# Sheet1.net
KiCad netlist of a schematic drawn in Altium Designer
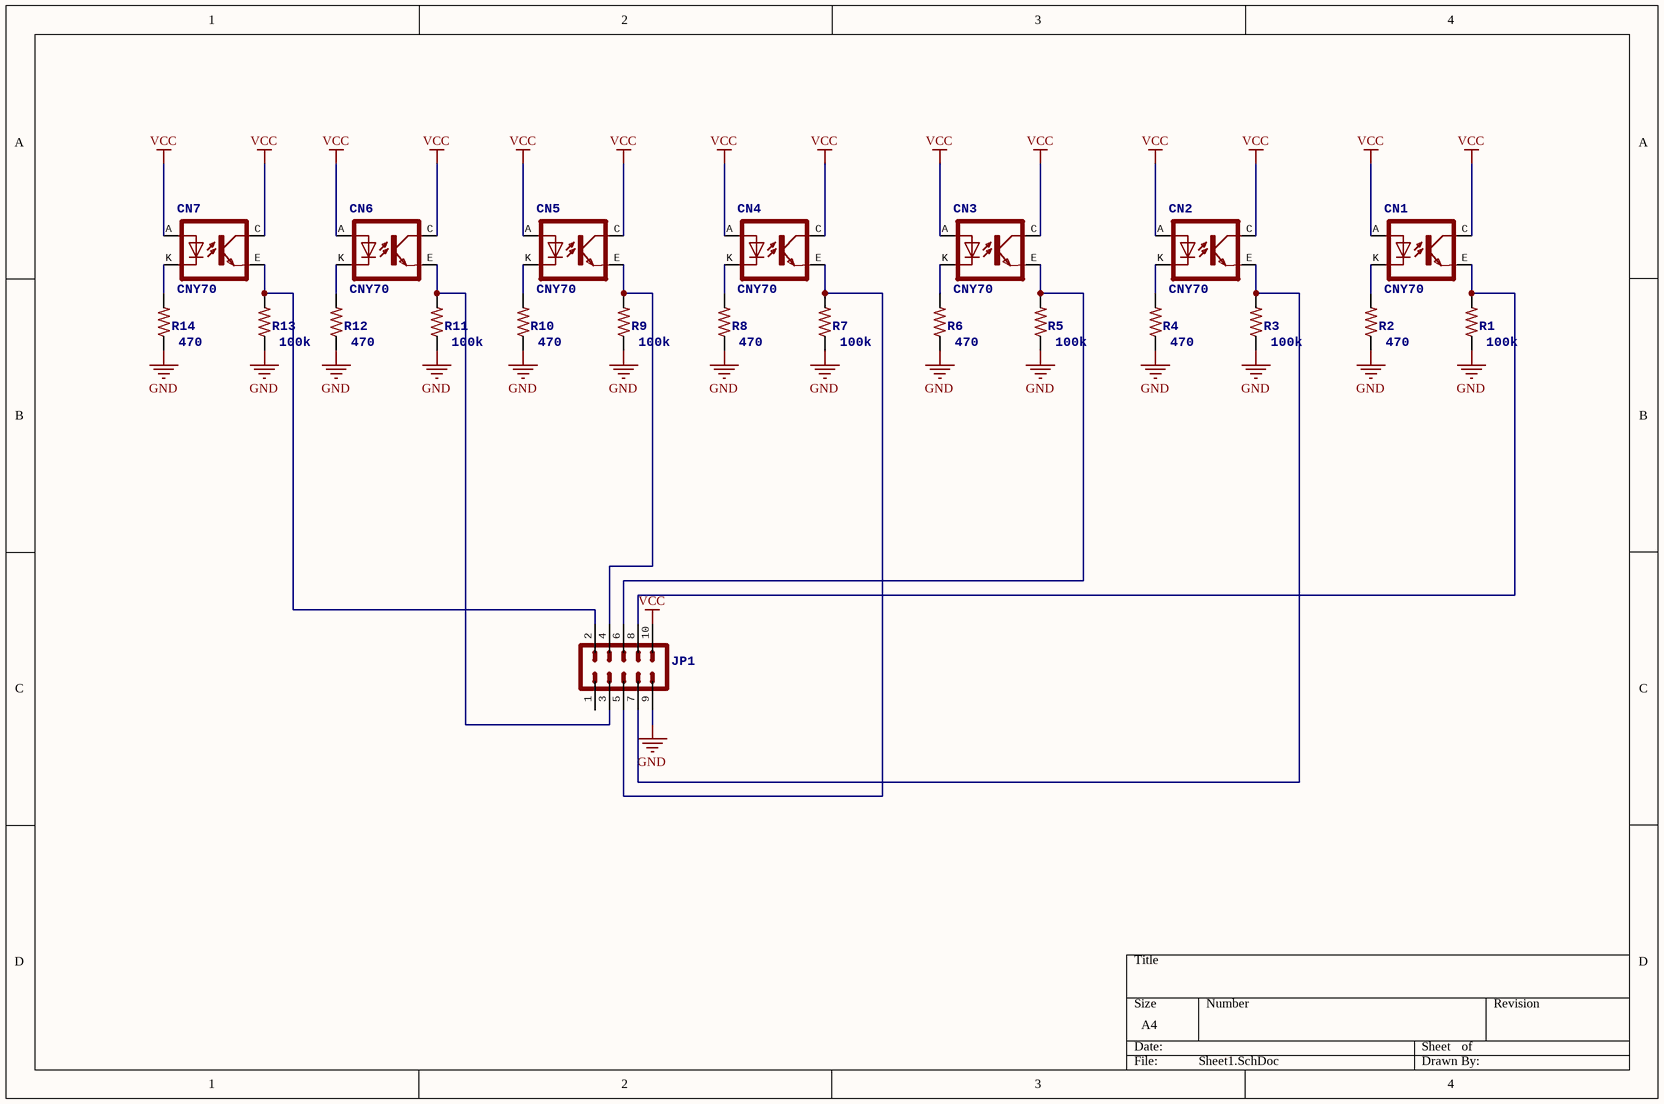
[diagram p0: Sheet1.SchDoc]

(export (version "E")
  (design (tool "Eeschema 10.0.6"))
  (components
    (comp (ref "CN1") (value "CNY70") (footprint "4") (libsource (lib "cny70") (part "CNY70")))
    (comp (ref "CN2") (value "CNY70") (footprint "4") (libsource (lib "cny70") (part "CNY70")))
    (comp (ref "CN3") (value "CNY70") (footprint "4") (libsource (lib "cny70") (part "CNY70")))
    (comp (ref "CN4") (value "CNY70") (footprint "4") (libsource (lib "cny70") (part "CNY70")))
    (comp (ref "CN5") (value "CNY70") (footprint "4") (libsource (lib "cny70") (part "CNY70")))
    (comp (ref "CN6") (value "CNY70") (footprint "4") (libsource (lib "cny70") (part "CNY70")))
    (comp (ref "CN7") (value "CNY70") (footprint "4") (libsource (lib "cny70") (part "CNY70")))
    (comp (ref "JP1")
      (value "Header 5x2Standard 10-pin dual row 0.1\" header. Commonly used with AVR-ISP. Use with Spark Fun Electronics SKU: PRT-00778")
      (footprint "2X5-SHROUDED_LOCK")
      (libsource (lib "SparkFun-Connectors") (part "M05X2SHD_LOCK"))
    )
    (comp (ref "R1")
      (value "100k")
      (footprint "AXIAL-0.4")
      (libsource (lib "SparkFun-Passives") (part "RESISTORPTH-1/4W"))
    )
    (comp (ref "R2")
      (value "470")
      (footprint "AXIAL-0.4")
      (libsource (lib "SparkFun-Passives") (part "RESISTORPTH-1/4W"))
    )
    (comp (ref "R3")
      (value "100k")
      (footprint "AXIAL-0.4")
      (libsource (lib "SparkFun-Passives") (part "RESISTORPTH-1/4W"))
    )
    (comp (ref "R4")
      (value "470")
      (footprint "AXIAL-0.4")
      (libsource (lib "SparkFun-Passives") (part "RESISTORPTH-1/4W"))
    )
    (comp (ref "R5")
      (value "100k")
      (footprint "AXIAL-0.4")
      (libsource (lib "SparkFun-Passives") (part "RESISTORPTH-1/4W"))
    )
    (comp (ref "R6")
      (value "470")
      (footprint "AXIAL-0.4")
      (libsource (lib "SparkFun-Passives") (part "RESISTORPTH-1/4W"))
    )
    (comp (ref "R7")
      (value "100k")
      (footprint "AXIAL-0.4")
      (libsource (lib "SparkFun-Passives") (part "RESISTORPTH-1/4W"))
    )
    (comp (ref "R8")
      (value "470")
      (footprint "AXIAL-0.4")
      (libsource (lib "SparkFun-Passives") (part "RESISTORPTH-1/4W"))
    )
    (comp (ref "R9")
      (value "100k")
      (footprint "AXIAL-0.4")
      (libsource (lib "SparkFun-Passives") (part "RESISTORPTH-1/4W"))
    )
    (comp (ref "R10")
      (value "470")
      (footprint "AXIAL-0.4")
      (libsource (lib "SparkFun-Passives") (part "RESISTORPTH-1/4W"))
    )
    (comp (ref "R11")
      (value "100k")
      (footprint "AXIAL-0.4")
      (libsource (lib "SparkFun-Passives") (part "RESISTORPTH-1/4W"))
    )
    (comp (ref "R12")
      (value "470")
      (footprint "AXIAL-0.4")
      (libsource (lib "SparkFun-Passives") (part "RESISTORPTH-1/4W"))
    )
    (comp (ref "R13")
      (value "100k")
      (footprint "AXIAL-0.4")
      (libsource (lib "SparkFun-Passives") (part "RESISTORPTH-1/4W"))
    )
    (comp (ref "R14")
      (value "470")
      (footprint "AXIAL-0.4")
      (libsource (lib "SparkFun-Passives") (part "RESISTORPTH-1/4W"))
    )
  )
  (nets
    (net (code "1") (name "GND") (class "Default")
      (node (ref "JP1") (pin "9") (pinfunction "9_9") (pintype "passive"))
      (node (ref "R1") (pin "P$1") (pinfunction "1_P$1") (pintype "passive"))
      (node (ref "R10") (pin "P$1") (pinfunction "1_P$1") (pintype "passive"))
      (node (ref "R11") (pin "P$1") (pinfunction "1_P$1") (pintype "passive"))
      (node (ref "R12") (pin "P$1") (pinfunction "1_P$1") (pintype "passive"))
      (node (ref "R13") (pin "P$1") (pinfunction "1_P$1") (pintype "passive"))
      (node (ref "R14") (pin "P$1") (pinfunction "1_P$1") (pintype "passive"))
      (node (ref "R2") (pin "P$1") (pinfunction "1_P$1") (pintype "passive"))
      (node (ref "R3") (pin "P$1") (pinfunction "1_P$1") (pintype "passive"))
      (node (ref "R4") (pin "P$1") (pinfunction "1_P$1") (pintype "passive"))
      (node (ref "R5") (pin "P$1") (pinfunction "1_P$1") (pintype "passive"))
      (node (ref "R6") (pin "P$1") (pinfunction "1_P$1") (pintype "passive"))
      (node (ref "R7") (pin "P$1") (pinfunction "1_P$1") (pintype "passive"))
      (node (ref "R8") (pin "P$1") (pinfunction "1_P$1") (pintype "passive"))
      (node (ref "R9") (pin "P$1") (pinfunction "1_P$1") (pintype "passive"))
    )
    (net (code "2") (name "Net-(CN1-C)") (class "Default")
      (node (ref "CN1") (pin "K") (pinfunction "C_K") (pintype "passive"))
      (node (ref "R2") (pin "P$2") (pinfunction "2_P$2") (pintype "passive"))
    )
    (net (code "3") (name "Net-(CN1-EMI)") (class "Default")
      (node (ref "CN1") (pin "E") (pinfunction "EMI_E") (pintype "passive"))
      (node (ref "JP1") (pin "8") (pinfunction "8_8") (pintype "passive"))
      (node (ref "R1") (pin "P$2") (pinfunction "2_P$2") (pintype "passive"))
    )
    (net (code "4") (name "Net-(CN2-C)") (class "Default")
      (node (ref "CN2") (pin "K") (pinfunction "C_K") (pintype "passive"))
      (node (ref "R4") (pin "P$2") (pinfunction "2_P$2") (pintype "passive"))
    )
    (net (code "5") (name "Net-(CN2-EMI)") (class "Default")
      (node (ref "CN2") (pin "E") (pinfunction "EMI_E") (pintype "passive"))
      (node (ref "JP1") (pin "7") (pinfunction "7_7") (pintype "passive"))
      (node (ref "R3") (pin "P$2") (pinfunction "2_P$2") (pintype "passive"))
    )
    (net (code "6") (name "Net-(CN3-C)") (class "Default")
      (node (ref "CN3") (pin "K") (pinfunction "C_K") (pintype "passive"))
      (node (ref "R6") (pin "P$2") (pinfunction "2_P$2") (pintype "passive"))
    )
    (net (code "7") (name "Net-(CN3-EMI)") (class "Default")
      (node (ref "CN3") (pin "E") (pinfunction "EMI_E") (pintype "passive"))
      (node (ref "JP1") (pin "6") (pinfunction "6_6") (pintype "passive"))
      (node (ref "R5") (pin "P$2") (pinfunction "2_P$2") (pintype "passive"))
    )
    (net (code "8") (name "Net-(CN4-C)") (class "Default")
      (node (ref "CN4") (pin "K") (pinfunction "C_K") (pintype "passive"))
      (node (ref "R8") (pin "P$2") (pinfunction "2_P$2") (pintype "passive"))
    )
    (net (code "9") (name "Net-(CN4-EMI)") (class "Default")
      (node (ref "CN4") (pin "E") (pinfunction "EMI_E") (pintype "passive"))
      (node (ref "JP1") (pin "5") (pinfunction "5_5") (pintype "passive"))
      (node (ref "R7") (pin "P$2") (pinfunction "2_P$2") (pintype "passive"))
    )
    (net (code "10") (name "Net-(CN5-C)") (class "Default")
      (node (ref "CN5") (pin "K") (pinfunction "C_K") (pintype "passive"))
      (node (ref "R10") (pin "P$2") (pinfunction "2_P$2") (pintype "passive"))
    )
    (net (code "11") (name "Net-(CN5-EMI)") (class "Default")
      (node (ref "CN5") (pin "E") (pinfunction "EMI_E") (pintype "passive"))
      (node (ref "JP1") (pin "4") (pinfunction "4_4") (pintype "passive"))
      (node (ref "R9") (pin "P$2") (pinfunction "2_P$2") (pintype "passive"))
    )
    (net (code "12") (name "Net-(CN6-C)") (class "Default")
      (node (ref "CN6") (pin "K") (pinfunction "C_K") (pintype "passive"))
      (node (ref "R12") (pin "P$2") (pinfunction "2_P$2") (pintype "passive"))
    )
    (net (code "13") (name "Net-(CN6-EMI)") (class "Default")
      (node (ref "CN6") (pin "E") (pinfunction "EMI_E") (pintype "passive"))
      (node (ref "JP1") (pin "3") (pinfunction "3_3") (pintype "passive"))
      (node (ref "R11") (pin "P$2") (pinfunction "2_P$2") (pintype "passive"))
    )
    (net (code "14") (name "Net-(CN7-C)") (class "Default")
      (node (ref "CN7") (pin "K") (pinfunction "C_K") (pintype "passive"))
      (node (ref "R14") (pin "P$2") (pinfunction "2_P$2") (pintype "passive"))
    )
    (net (code "15") (name "Net-(CN7-EMI)") (class "Default")
      (node (ref "CN7") (pin "E") (pinfunction "EMI_E") (pintype "passive"))
      (node (ref "JP1") (pin "2") (pinfunction "2_2") (pintype "passive"))
      (node (ref "R13") (pin "P$2") (pinfunction "2_P$2") (pintype "passive"))
    )
    (net (code "16") (name "VCC") (class "Default")
      (node (ref "CN1") (pin "A") (pinfunction "A_A") (pintype "passive"))
      (node (ref "CN1") (pin "C") (pinfunction "COL_C") (pintype "passive"))
      (node (ref "CN2") (pin "A") (pinfunction "A_A") (pintype "passive"))
      (node (ref "CN2") (pin "C") (pinfunction "COL_C") (pintype "passive"))
      (node (ref "CN3") (pin "A") (pinfunction "A_A") (pintype "passive"))
      (node (ref "CN3") (pin "C") (pinfunction "COL_C") (pintype "passive"))
      (node (ref "CN4") (pin "A") (pinfunction "A_A") (pintype "passive"))
      (node (ref "CN4") (pin "C") (pinfunction "COL_C") (pintype "passive"))
      (node (ref "CN5") (pin "A") (pinfunction "A_A") (pintype "passive"))
      (node (ref "CN5") (pin "C") (pinfunction "COL_C") (pintype "passive"))
      (node (ref "CN6") (pin "A") (pinfunction "A_A") (pintype "passive"))
      (node (ref "CN6") (pin "C") (pinfunction "COL_C") (pintype "passive"))
      (node (ref "CN7") (pin "A") (pinfunction "A_A") (pintype "passive"))
      (node (ref "CN7") (pin "C") (pinfunction "COL_C") (pintype "passive"))
      (node (ref "JP1") (pin "10") (pinfunction "10_10") (pintype "passive"))
    )
    (net (code "17") (name "unconnected-(JP1-Pad1)") (class "Default")
      (node (ref "JP1") (pin "1") (pinfunction "1_1") (pintype "passive"))
    )
  )
)
